# M205X.net
KiCad netlist of a schematic drawn in EAGLE
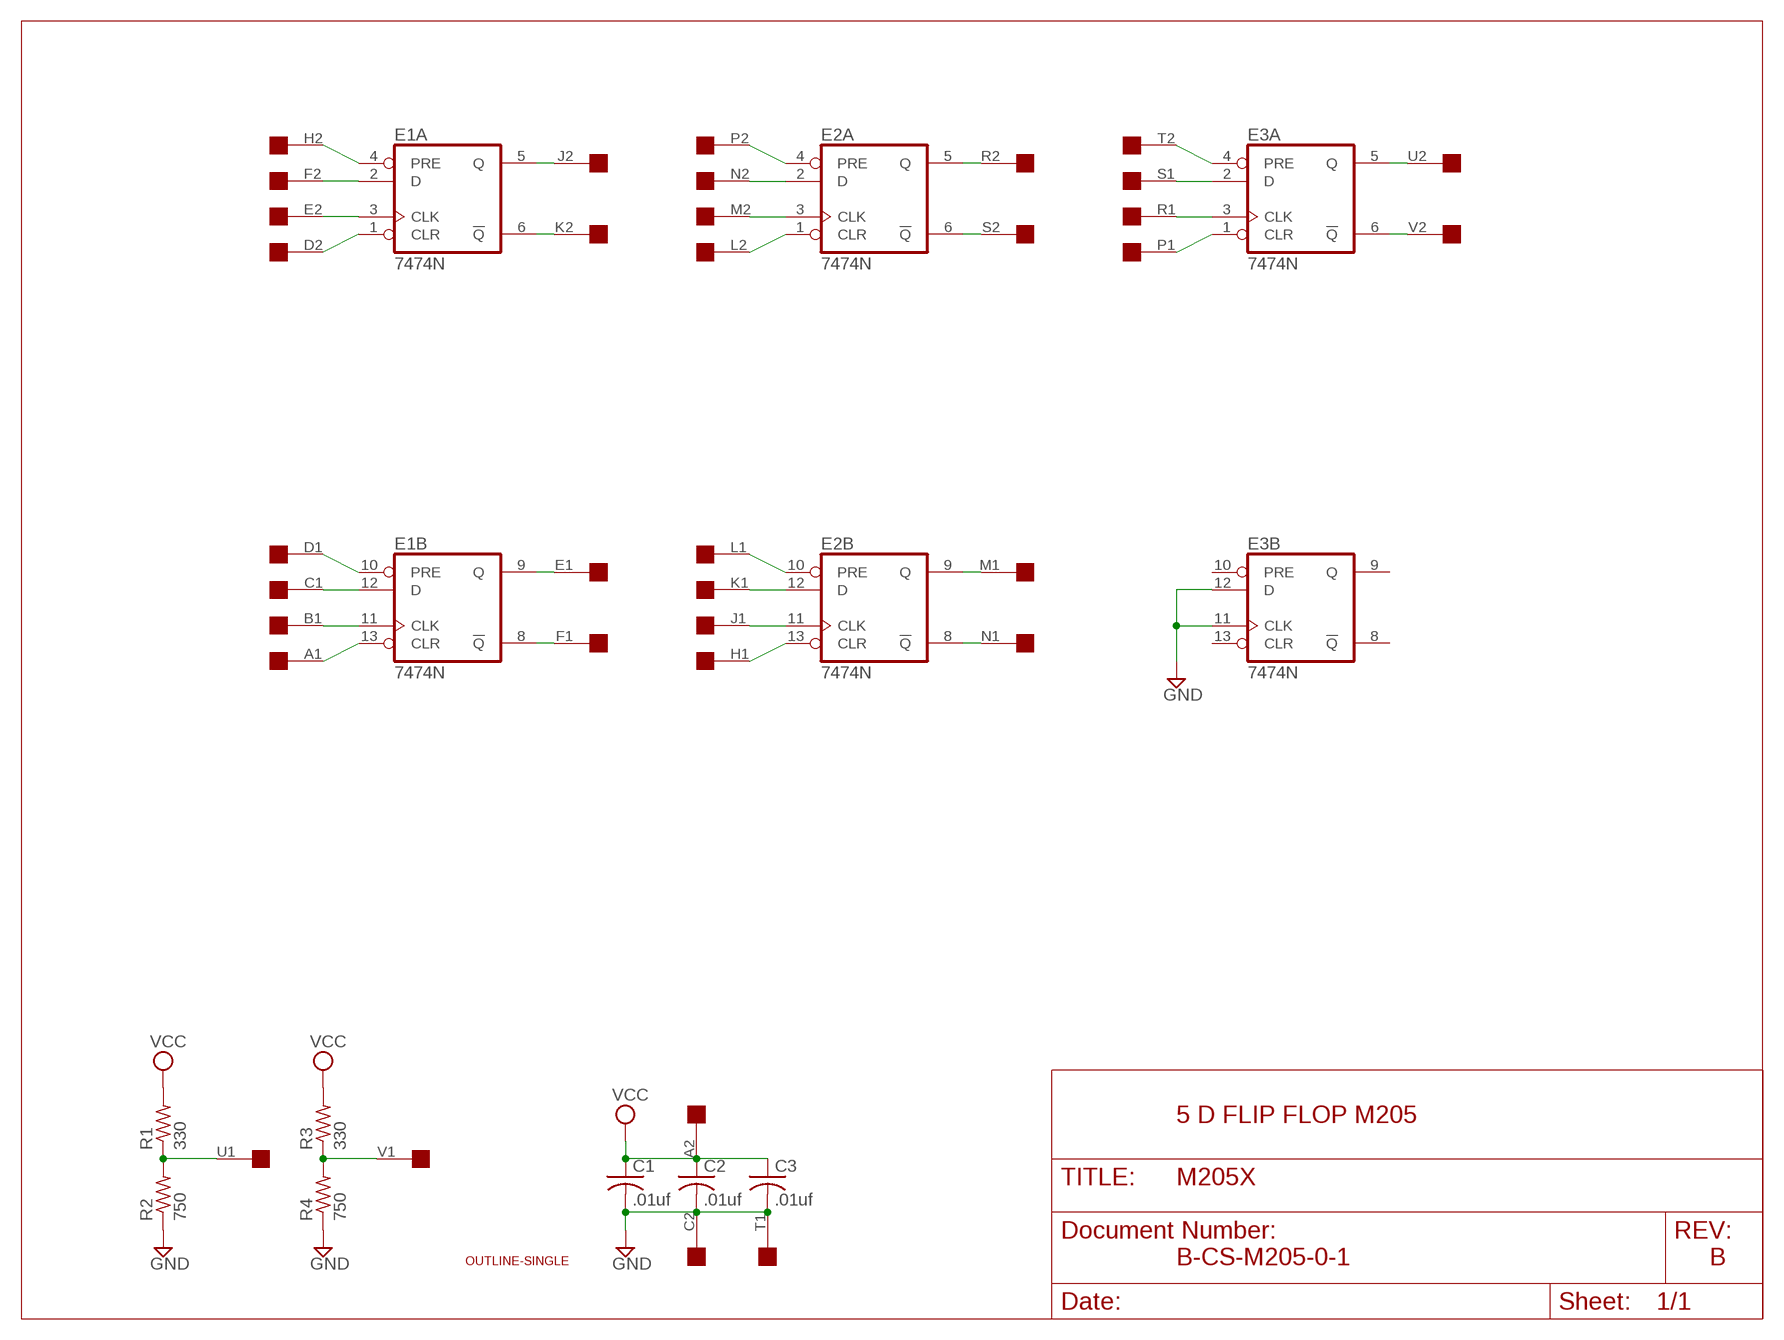
[diagram p0: schematic, sheet 1]

(export (version "E")
  (design (tool "Eeschema 10.0.6"))
  (components
    (comp (ref "C1")
      (value ".01uf")
      (footprint "eagle-import:C050-025X075")
      (libsource (lib "eagle-import") (part "C-US050-025X075"))
    )
    (comp (ref "C2")
      (value ".01uf")
      (footprint "eagle-import:C050-025X075")
      (libsource (lib "eagle-import") (part "C-US050-025X075"))
    )
    (comp (ref "C3")
      (value ".01uf")
      (footprint "eagle-import:C050-025X075")
      (libsource (lib "eagle-import") (part "C-US050-025X075"))
    )
    (comp (ref "E1")
      (value "7474N")
      (footprint "eagle-import:DIL14")
      (libsource (lib "eagle-import") (part "7474NS"))
    )
    (comp (ref "E2")
      (value "7474N")
      (footprint "eagle-import:DIL14")
      (libsource (lib "eagle-import") (part "7474NS"))
    )
    (comp (ref "E3")
      (value "7474N")
      (footprint "eagle-import:DIL14")
      (libsource (lib "eagle-import") (part "7474NS"))
    )
    (comp (ref "R1")
      (value "330")
      (footprint "eagle-import:0207_10")
      (libsource (lib "eagle-import") (part "R-US_0207/10"))
    )
    (comp (ref "R2")
      (value "750")
      (footprint "eagle-import:0207_10")
      (libsource (lib "eagle-import") (part "R-US_0207/10"))
    )
    (comp (ref "R3")
      (value "330")
      (footprint "eagle-import:0207_10")
      (libsource (lib "eagle-import") (part "R-US_0207/10"))
    )
    (comp (ref "R4")
      (value "750")
      (footprint "eagle-import:0207_10")
      (libsource (lib "eagle-import") (part "R-US_0207/10"))
    )
    (comp (ref "U$1")
      (value "OUTLINE-SINGLE")
      (footprint "eagle-import:SINGLE")
      (libsource (lib "eagle-import") (part "OUTLINE-SINGLE"))
    )
    (comp (ref "U$2")
      (value "EDGE-2CONNECTOR")
      (footprint "eagle-import:EDGE-CON2")
      (libsource (lib "eagle-import") (part "EDGE-2CONNECTOR"))
    )
  )
  (nets
    (net (code "1") (name "GND") (class "Default")
      (node (ref "C1") (pin "2") (pinfunction "2_2") (pintype "passive"))
      (node (ref "C2") (pin "2") (pinfunction "2_2") (pintype "passive"))
      (node (ref "C3") (pin "2") (pinfunction "2_2") (pintype "passive"))
      (node (ref "E3") (pin "11") (pinfunction "CLK_11") (pintype "input"))
      (node (ref "E3") (pin "12") (pinfunction "D_12") (pintype "input"))
      (node (ref "R2") (pin "1") (pinfunction "1_1") (pintype "passive"))
      (node (ref "R4") (pin "1") (pinfunction "1_1") (pintype "passive"))
      (node (ref "U$2") (pin "C2") (pinfunction "1_C2") (pintype "bidirectional"))
      (node (ref "U$2") (pin "T1") (pinfunction "1_T1") (pintype "bidirectional"))
    )
    (net (code "2") (name "Net-(E1A-CLK)") (class "Default")
      (node (ref "E1") (pin "3") (pinfunction "CLK_3") (pintype "input"))
      (node (ref "U$2") (pin "E2") (pinfunction "1_E2") (pintype "bidirectional"))
    )
    (net (code "3") (name "Net-(E1A-CLR)") (class "Default")
      (node (ref "E1") (pin "1") (pinfunction "CLR_1") (pintype "input"))
      (node (ref "U$2") (pin "D2") (pinfunction "1_D2") (pintype "bidirectional"))
    )
    (net (code "4") (name "Net-(E1A-D)") (class "Default")
      (node (ref "E1") (pin "2") (pinfunction "D_2") (pintype "input"))
      (node (ref "U$2") (pin "F2") (pinfunction "1_F2") (pintype "bidirectional"))
    )
    (net (code "5") (name "Net-(E1A-PRE)") (class "Default")
      (node (ref "E1") (pin "4") (pinfunction "PRE_4") (pintype "input"))
      (node (ref "U$2") (pin "H2") (pinfunction "1_H2") (pintype "bidirectional"))
    )
    (net (code "6") (name "Net-(E1A-Q)") (class "Default")
      (node (ref "E1") (pin "5") (pinfunction "Q_5") (pintype "output"))
      (node (ref "U$2") (pin "J2") (pinfunction "1_J2") (pintype "bidirectional"))
    )
    (net (code "7") (name "Net-(E1A-~{Q})") (class "Default")
      (node (ref "E1") (pin "6") (pinfunction "~{Q}_6") (pintype "output"))
      (node (ref "U$2") (pin "K2") (pinfunction "1_K2") (pintype "bidirectional"))
    )
    (net (code "8") (name "Net-(E1B-CLK)") (class "Default")
      (node (ref "E1") (pin "11") (pinfunction "CLK_11") (pintype "input"))
      (node (ref "U$2") (pin "B1") (pinfunction "1_B1") (pintype "bidirectional"))
    )
    (net (code "9") (name "Net-(E1B-CLR)") (class "Default")
      (node (ref "E1") (pin "13") (pinfunction "CLR_13") (pintype "input"))
      (node (ref "U$2") (pin "A1") (pinfunction "1_A1") (pintype "bidirectional"))
    )
    (net (code "10") (name "Net-(E1B-D)") (class "Default")
      (node (ref "E1") (pin "12") (pinfunction "D_12") (pintype "input"))
      (node (ref "U$2") (pin "C1") (pinfunction "1_C1") (pintype "bidirectional"))
    )
    (net (code "11") (name "Net-(E1B-PRE)") (class "Default")
      (node (ref "E1") (pin "10") (pinfunction "PRE_10") (pintype "input"))
      (node (ref "U$2") (pin "D1") (pinfunction "1_D1") (pintype "bidirectional"))
    )
    (net (code "12") (name "Net-(E1B-Q)") (class "Default")
      (node (ref "E1") (pin "9") (pinfunction "Q_9") (pintype "output"))
      (node (ref "U$2") (pin "E1") (pinfunction "1_E1") (pintype "bidirectional"))
    )
    (net (code "13") (name "Net-(E1B-~{Q})") (class "Default")
      (node (ref "E1") (pin "8") (pinfunction "~{Q}_8") (pintype "output"))
      (node (ref "U$2") (pin "F1") (pinfunction "1_F1") (pintype "bidirectional"))
    )
    (net (code "14") (name "Net-(E2A-CLK)") (class "Default")
      (node (ref "E2") (pin "3") (pinfunction "CLK_3") (pintype "input"))
      (node (ref "U$2") (pin "M2") (pinfunction "1_M2") (pintype "bidirectional"))
    )
    (net (code "15") (name "Net-(E2A-CLR)") (class "Default")
      (node (ref "E2") (pin "1") (pinfunction "CLR_1") (pintype "input"))
      (node (ref "U$2") (pin "L2") (pinfunction "1_L2") (pintype "bidirectional"))
    )
    (net (code "16") (name "Net-(E2A-D)") (class "Default")
      (node (ref "E2") (pin "2") (pinfunction "D_2") (pintype "input"))
      (node (ref "U$2") (pin "N2") (pinfunction "1_N2") (pintype "bidirectional"))
    )
    (net (code "17") (name "Net-(E2A-PRE)") (class "Default")
      (node (ref "E2") (pin "4") (pinfunction "PRE_4") (pintype "input"))
      (node (ref "U$2") (pin "P2") (pinfunction "1_P2") (pintype "bidirectional"))
    )
    (net (code "18") (name "Net-(E2A-Q)") (class "Default")
      (node (ref "E2") (pin "5") (pinfunction "Q_5") (pintype "output"))
      (node (ref "U$2") (pin "R2") (pinfunction "1_R2") (pintype "bidirectional"))
    )
    (net (code "19") (name "Net-(E2A-~{Q})") (class "Default")
      (node (ref "E2") (pin "6") (pinfunction "~{Q}_6") (pintype "output"))
      (node (ref "U$2") (pin "S2") (pinfunction "1_S2") (pintype "bidirectional"))
    )
    (net (code "20") (name "Net-(E2B-CLK)") (class "Default")
      (node (ref "E2") (pin "11") (pinfunction "CLK_11") (pintype "input"))
      (node (ref "U$2") (pin "J1") (pinfunction "1_J1") (pintype "bidirectional"))
    )
    (net (code "21") (name "Net-(E2B-CLR)") (class "Default")
      (node (ref "E2") (pin "13") (pinfunction "CLR_13") (pintype "input"))
      (node (ref "U$2") (pin "H1") (pinfunction "1_H1") (pintype "bidirectional"))
    )
    (net (code "22") (name "Net-(E2B-D)") (class "Default")
      (node (ref "E2") (pin "12") (pinfunction "D_12") (pintype "input"))
      (node (ref "U$2") (pin "K1") (pinfunction "1_K1") (pintype "bidirectional"))
    )
    (net (code "23") (name "Net-(E2B-PRE)") (class "Default")
      (node (ref "E2") (pin "10") (pinfunction "PRE_10") (pintype "input"))
      (node (ref "U$2") (pin "L1") (pinfunction "1_L1") (pintype "bidirectional"))
    )
    (net (code "24") (name "Net-(E2B-Q)") (class "Default")
      (node (ref "E2") (pin "9") (pinfunction "Q_9") (pintype "output"))
      (node (ref "U$2") (pin "M1") (pinfunction "1_M1") (pintype "bidirectional"))
    )
    (net (code "25") (name "Net-(E2B-~{Q})") (class "Default")
      (node (ref "E2") (pin "8") (pinfunction "~{Q}_8") (pintype "output"))
      (node (ref "U$2") (pin "N1") (pinfunction "1_N1") (pintype "bidirectional"))
    )
    (net (code "26") (name "Net-(E3A-CLK)") (class "Default")
      (node (ref "E3") (pin "3") (pinfunction "CLK_3") (pintype "input"))
      (node (ref "U$2") (pin "R1") (pinfunction "1_R1") (pintype "bidirectional"))
    )
    (net (code "27") (name "Net-(E3A-CLR)") (class "Default")
      (node (ref "E3") (pin "1") (pinfunction "CLR_1") (pintype "input"))
      (node (ref "U$2") (pin "P1") (pinfunction "1_P1") (pintype "bidirectional"))
    )
    (net (code "28") (name "Net-(E3A-D)") (class "Default")
      (node (ref "E3") (pin "2") (pinfunction "D_2") (pintype "input"))
      (node (ref "U$2") (pin "S1") (pinfunction "1_S1") (pintype "bidirectional"))
    )
    (net (code "29") (name "Net-(E3A-PRE)") (class "Default")
      (node (ref "E3") (pin "4") (pinfunction "PRE_4") (pintype "input"))
      (node (ref "U$2") (pin "T2") (pinfunction "1_T2") (pintype "bidirectional"))
    )
    (net (code "30") (name "Net-(E3A-Q)") (class "Default")
      (node (ref "E3") (pin "5") (pinfunction "Q_5") (pintype "output"))
      (node (ref "U$2") (pin "U2") (pinfunction "1_U2") (pintype "bidirectional"))
    )
    (net (code "31") (name "Net-(E3A-~{Q})") (class "Default")
      (node (ref "E3") (pin "6") (pinfunction "~{Q}_6") (pintype "output"))
      (node (ref "U$2") (pin "V2") (pinfunction "1_V2") (pintype "bidirectional"))
    )
    (net (code "32") (name "Net-(U$2AG-1)") (class "Default")
      (node (ref "R1") (pin "1") (pinfunction "1_1") (pintype "passive"))
      (node (ref "R2") (pin "2") (pinfunction "2_2") (pintype "passive"))
      (node (ref "U$2") (pin "U1") (pinfunction "1_U1") (pintype "bidirectional"))
    )
    (net (code "33") (name "Net-(U$2AI-1)") (class "Default")
      (node (ref "R3") (pin "1") (pinfunction "1_1") (pintype "passive"))
      (node (ref "R4") (pin "2") (pinfunction "2_2") (pintype "passive"))
      (node (ref "U$2") (pin "V1") (pinfunction "1_V1") (pintype "bidirectional"))
    )
    (net (code "34") (name "VCC") (class "Default")
      (node (ref "C1") (pin "1") (pinfunction "1_1") (pintype "passive"))
      (node (ref "C2") (pin "1") (pinfunction "1_1") (pintype "passive"))
      (node (ref "C3") (pin "1") (pinfunction "1_1") (pintype "passive"))
      (node (ref "R1") (pin "2") (pinfunction "2_2") (pintype "passive"))
      (node (ref "R3") (pin "2") (pinfunction "2_2") (pintype "passive"))
      (node (ref "U$2") (pin "A2") (pinfunction "1_A2") (pintype "bidirectional"))
    )
    (net (code "35") (name "unconnected-(E3B-CLR-Pad13)") (class "Default")
      (node (ref "E3") (pin "13") (pinfunction "CLR_13") (pintype "input"))
    )
    (net (code "36") (name "unconnected-(E3B-PRE-Pad10)") (class "Default")
      (node (ref "E3") (pin "10") (pinfunction "PRE_10") (pintype "input"))
    )
    (net (code "37") (name "unconnected-(E3B-Q-Pad9)") (class "Default")
      (node (ref "E3") (pin "9") (pinfunction "Q_9") (pintype "output"))
    )
    (net (code "38") (name "unconnected-(E3B-~{Q}-Pad8)") (class "Default")
      (node (ref "E3") (pin "8") (pinfunction "~{Q}_8") (pintype "output"))
    )
  )
)
